# mech_comp.net
KiCad netlist of a schematic drawn in Altium Designer
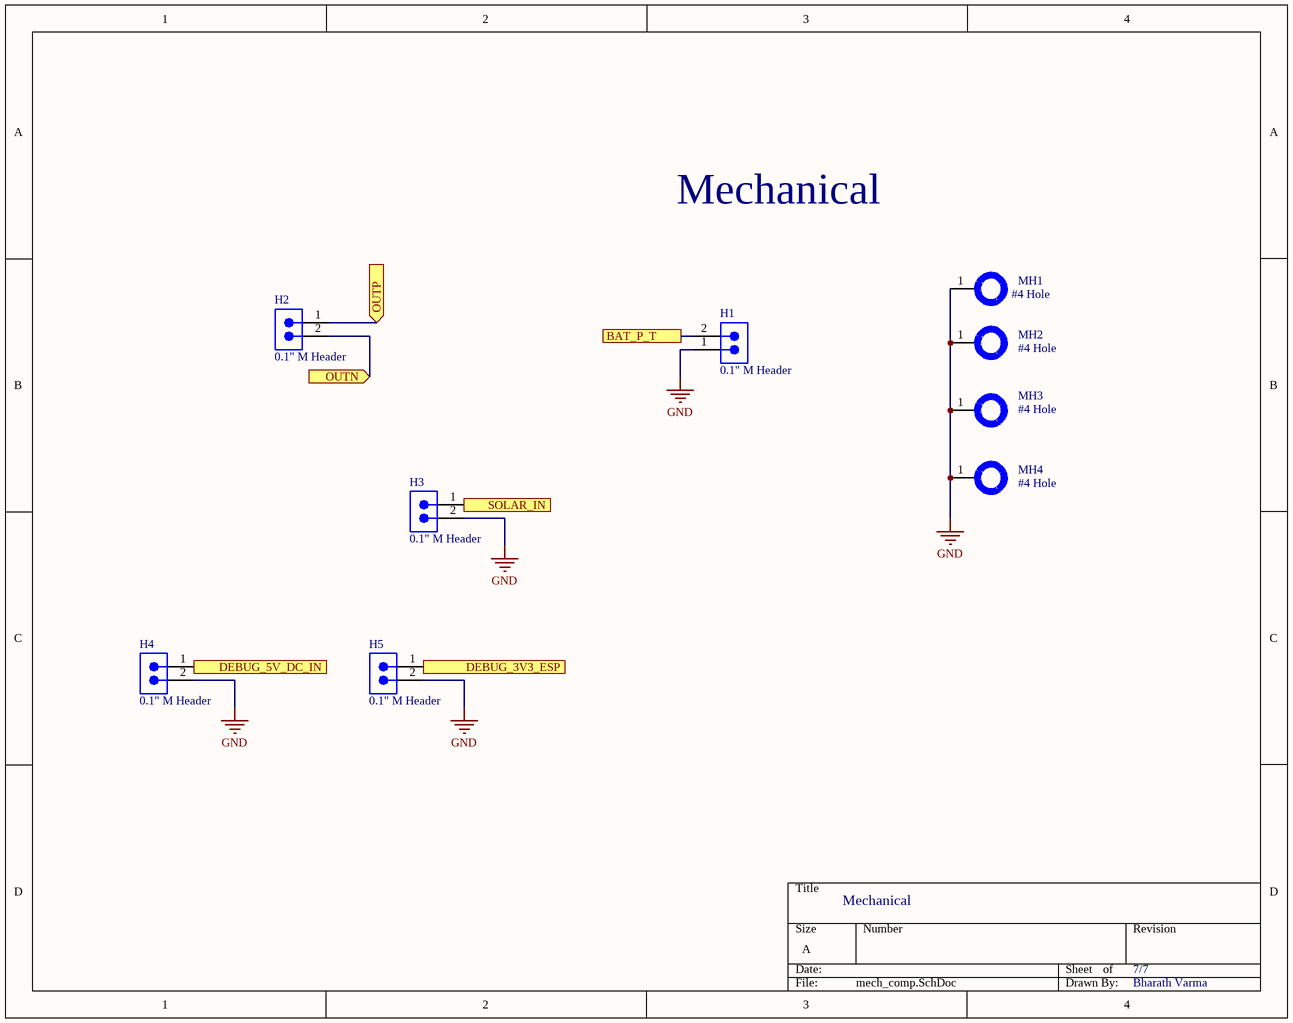
[diagram p0: mech_comp.SchDoc]

(export (version "E")
  (design (tool "Eeschema 10.0.6"))
  (components
    (comp (ref "H1")
      (value "0.1\" M Header")
      (footprint "2-PIN_MALE_HEADER_01-IN")
      (description "CONN HEADER VERT 2POS 2.54MM")
      (fields
        (field (name "MANUFACTURER") "Sullins")
        (field (name "MANUFACTURER PART NUMBER") "PRPC002SAAN-RC")
      )
      (libsource (lib "LPEDT_Pulse_Project_Int_Lib") (part "PRPC002SAAN-RC"))
    )
    (comp (ref "H2")
      (value "0.1\" M Header")
      (footprint "2-PIN_MALE_HEADER_01-IN")
      (description "CONN HEADER VERT 2POS 2.54MM")
      (fields
        (field (name "MANUFACTURER") "Sullins")
        (field (name "MANUFACTURER PART NUMBER") "PRPC002SAAN-RC")
      )
      (libsource (lib "LPEDT_Pulse_Project_Int_Lib") (part "PRPC002SAAN-RC"))
    )
    (comp (ref "H3")
      (value "0.1\" M Header")
      (footprint "2-PIN_MALE_HEADER_01-IN")
      (description "CONN HEADER VERT 2POS 2.54MM")
      (fields
        (field (name "MANUFACTURER") "Sullins")
        (field (name "MANUFACTURER PART NUMBER") "PRPC002SAAN-RC")
      )
      (libsource (lib "LPEDT_Pulse_Project_SCH_Library") (part "PRPC002SAAN-RC"))
    )
    (comp (ref "H4")
      (value "0.1\" M Header")
      (footprint "2-PIN_MALE_HEADER_01-IN")
      (description "CONN HEADER VERT 2POS 2.54MM")
      (fields
        (field (name "MANUFACTURER") "Sullins")
        (field (name "MANUFACTURER PART NUMBER") "PRPC002SAAN-RC")
      )
      (libsource (lib "LPEDT_Pulse_Project_SCH_Library") (part "PRPC002SAAN-RC"))
    )
    (comp (ref "H5")
      (value "0.1\" M Header")
      (footprint "2-PIN_MALE_HEADER_01-IN")
      (description "CONN HEADER VERT 2POS 2.54MM")
      (fields
        (field (name "MANUFACTURER") "Sullins")
        (field (name "MANUFACTURER PART NUMBER") "PRPC002SAAN-RC")
      )
      (libsource (lib "LPEDT_Pulse_Project_SCH_Library") (part "PRPC002SAAN-RC"))
    )
    (comp (ref "MH1")
      (value "#4 Hole")
      (footprint "HOLE_#4")
      (libsource (lib "LPEDT_Parts_Latest_updated_5") (part "HOLE_#4"))
    )
    (comp (ref "MH2")
      (value "#4 Hole")
      (footprint "HOLE_#4")
      (libsource (lib "LPEDT_Parts_Latest_updated_5") (part "HOLE_#4"))
    )
    (comp (ref "MH3")
      (value "#4 Hole")
      (footprint "HOLE_#4")
      (libsource (lib "LPEDT_Parts_Latest_updated_5") (part "HOLE_#4"))
    )
    (comp (ref "MH4")
      (value "#4 Hole")
      (footprint "HOLE_#4")
      (libsource (lib "LPEDT_Parts_Latest_updated_5") (part "HOLE_#4"))
    )
  )
  (nets
    (net (code "1") (name "/BAT_P_T") (class "Default")
      (node (ref "H1") (pin "2") (pinfunction "2_2") (pintype "passive"))
    )
    (net (code "2") (name "/DEBUG_3V3_ESP") (class "Default")
      (node (ref "H5") (pin "1") (pinfunction "1_1") (pintype "passive"))
    )
    (net (code "3") (name "/DEBUG_5V_DC_IN") (class "Default")
      (node (ref "H4") (pin "1") (pinfunction "1_1") (pintype "passive"))
    )
    (net (code "4") (name "/OUTN") (class "Default")
      (node (ref "H2") (pin "2") (pinfunction "2_2") (pintype "passive"))
    )
    (net (code "5") (name "/OUTP") (class "Default")
      (node (ref "H2") (pin "1") (pinfunction "1_1") (pintype "passive"))
    )
    (net (code "6") (name "/SOLAR_IN") (class "Default")
      (node (ref "H3") (pin "1") (pinfunction "1_1") (pintype "passive"))
    )
    (net (code "7") (name "GND") (class "Default")
      (node (ref "H1") (pin "1") (pinfunction "1_1") (pintype "passive"))
      (node (ref "H3") (pin "2") (pinfunction "2_2") (pintype "passive"))
      (node (ref "H4") (pin "2") (pinfunction "2_2") (pintype "passive"))
      (node (ref "H5") (pin "2") (pinfunction "2_2") (pintype "passive"))
      (node (ref "MH1") (pin "1") (pinfunction "1_1") (pintype "passive"))
      (node (ref "MH2") (pin "1") (pinfunction "1_1") (pintype "passive"))
      (node (ref "MH3") (pin "1") (pinfunction "1_1") (pintype "passive"))
      (node (ref "MH4") (pin "1") (pinfunction "1_1") (pintype "passive"))
    )
  )
)
